# Parlante.net
KiCad netlist of a schematic drawn in EAGLE
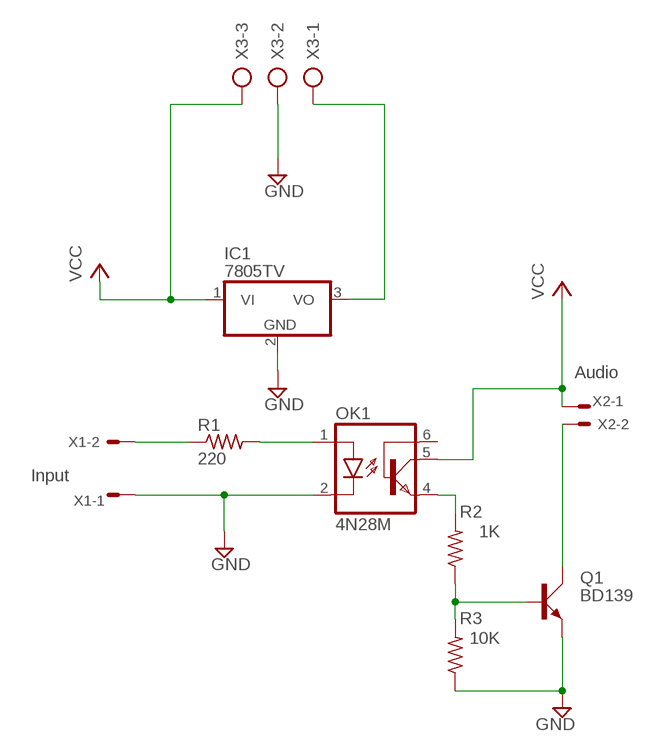
[diagram p0: schematic, sheet 1]

(export (version "E")
  (design (tool "Eeschema 10.0.6"))
  (components
    (comp (ref "IC1")
      (value "7805TV")
      (footprint "eagle-import:TO220V")
      (libsource (lib "eagle-import") (part "78TV05"))
    )
    (comp (ref "OK1")
      (value "4N28M")
      (footprint "eagle-import:DIL06")
      (fields (field (name "MF") "FAIRCHILD SEMICONDUCTOR") (field (name "MPN") "4N28-M"))
      (libsource (lib "eagle-import") (part "4N?M28"))
    )
    (comp (ref "Q1")
      (value "BD139")
      (footprint "eagle-import:TO126AV")
      (libsource (lib "eagle-import") (part "BD139"))
    )
    (comp (ref "R1")
      (value "220")
      (footprint "eagle-import:0204_7")
      (libsource (lib "eagle-import") (part "R-US_0204/7"))
    )
    (comp (ref "R2")
      (value "1K")
      (footprint "eagle-import:0204_7")
      (libsource (lib "eagle-import") (part "R-US_0204/7"))
    )
    (comp (ref "R3")
      (value "10K")
      (footprint "eagle-import:0204_7")
      (libsource (lib "eagle-import") (part "R-US_0204/7"))
    )
    (comp (ref "X1")
      (value "Input")
      (footprint "eagle-import:22-23-2021")
      (fields (field (name "MF") "MOLEX") (field (name "MPN") "22-23-2021"))
      (libsource (lib "eagle-import") (part "22-23-2021"))
    )
    (comp (ref "X2")
      (value "Audio")
      (footprint "eagle-import:22-23-2021")
      (fields (field (name "MF") "MOLEX") (field (name "MPN") "22-23-2021"))
      (libsource (lib "eagle-import") (part "22-23-2021"))
    )
    (comp (ref "X3")
      (value "AK500/3")
      (footprint "eagle-import:AK500_3")
      (libsource (lib "eagle-import") (part "AK500/3"))
    )
  )
  (nets
    (net (code "1") (name "GND") (class "Default")
      (node (ref "IC1") (pin "2") (pinfunction "GND_2") (pintype "passive"))
      (node (ref "OK1") (pin "2") (pinfunction "C_2") (pintype "passive"))
      (node (ref "Q1") (pin "E") (pinfunction "E_E") (pintype "passive"))
      (node (ref "R3") (pin "1") (pinfunction "1_1") (pintype "passive"))
      (node (ref "X1") (pin "1") (pinfunction "S_1") (pintype "passive"))
      (node (ref "X3") (pin "2") (pinfunction "KL_2") (pintype "passive"))
    )
    (net (code "2") (name "Net-(IC1-VO)") (class "Default")
      (node (ref "IC1") (pin "3") (pinfunction "VO_3") (pintype "passive"))
      (node (ref "X3") (pin "1") (pinfunction "KL_1") (pintype "passive"))
    )
    (net (code "3") (name "Net-(OK1-A)") (class "Default")
      (node (ref "OK1") (pin "1") (pinfunction "A_1") (pintype "passive"))
      (node (ref "R1") (pin "2") (pinfunction "2_2") (pintype "passive"))
    )
    (net (code "4") (name "Net-(OK1-EMI)") (class "Default")
      (node (ref "OK1") (pin "4") (pinfunction "EMI_4") (pintype "passive"))
      (node (ref "R2") (pin "2") (pinfunction "2_2") (pintype "passive"))
    )
    (net (code "5") (name "Net-(Q1-PadB)") (class "Default")
      (node (ref "Q1") (pin "B") (pinfunction "B_B") (pintype "passive"))
      (node (ref "R2") (pin "1") (pinfunction "1_1") (pintype "passive"))
      (node (ref "R3") (pin "2") (pinfunction "2_2") (pintype "passive"))
    )
    (net (code "6") (name "Net-(X1B-S)") (class "Default")
      (node (ref "R1") (pin "1") (pinfunction "1_1") (pintype "passive"))
      (node (ref "X1") (pin "2") (pinfunction "S_2") (pintype "passive"))
    )
    (net (code "7") (name "Net-(X2B-S)") (class "Default")
      (node (ref "Q1") (pin "C") (pinfunction "C_C") (pintype "passive"))
      (node (ref "X2") (pin "2") (pinfunction "S_2") (pintype "passive"))
    )
    (net (code "8") (name "VCC") (class "Default")
      (node (ref "IC1") (pin "1") (pinfunction "VI_1") (pintype "input"))
      (node (ref "OK1") (pin "5") (pinfunction "COL_5") (pintype "passive"))
      (node (ref "X2") (pin "1") (pinfunction "S_1") (pintype "passive"))
      (node (ref "X3") (pin "3") (pinfunction "KL_3") (pintype "passive"))
    )
    (net (code "9") (name "unconnected-(OK1-BAS-Pad6)") (class "Default")
      (node (ref "OK1") (pin "6") (pinfunction "BAS_6") (pintype "passive"))
    )
  )
)
